# 10-JTAG.net
KiCad netlist of a schematic drawn in Altium Designer
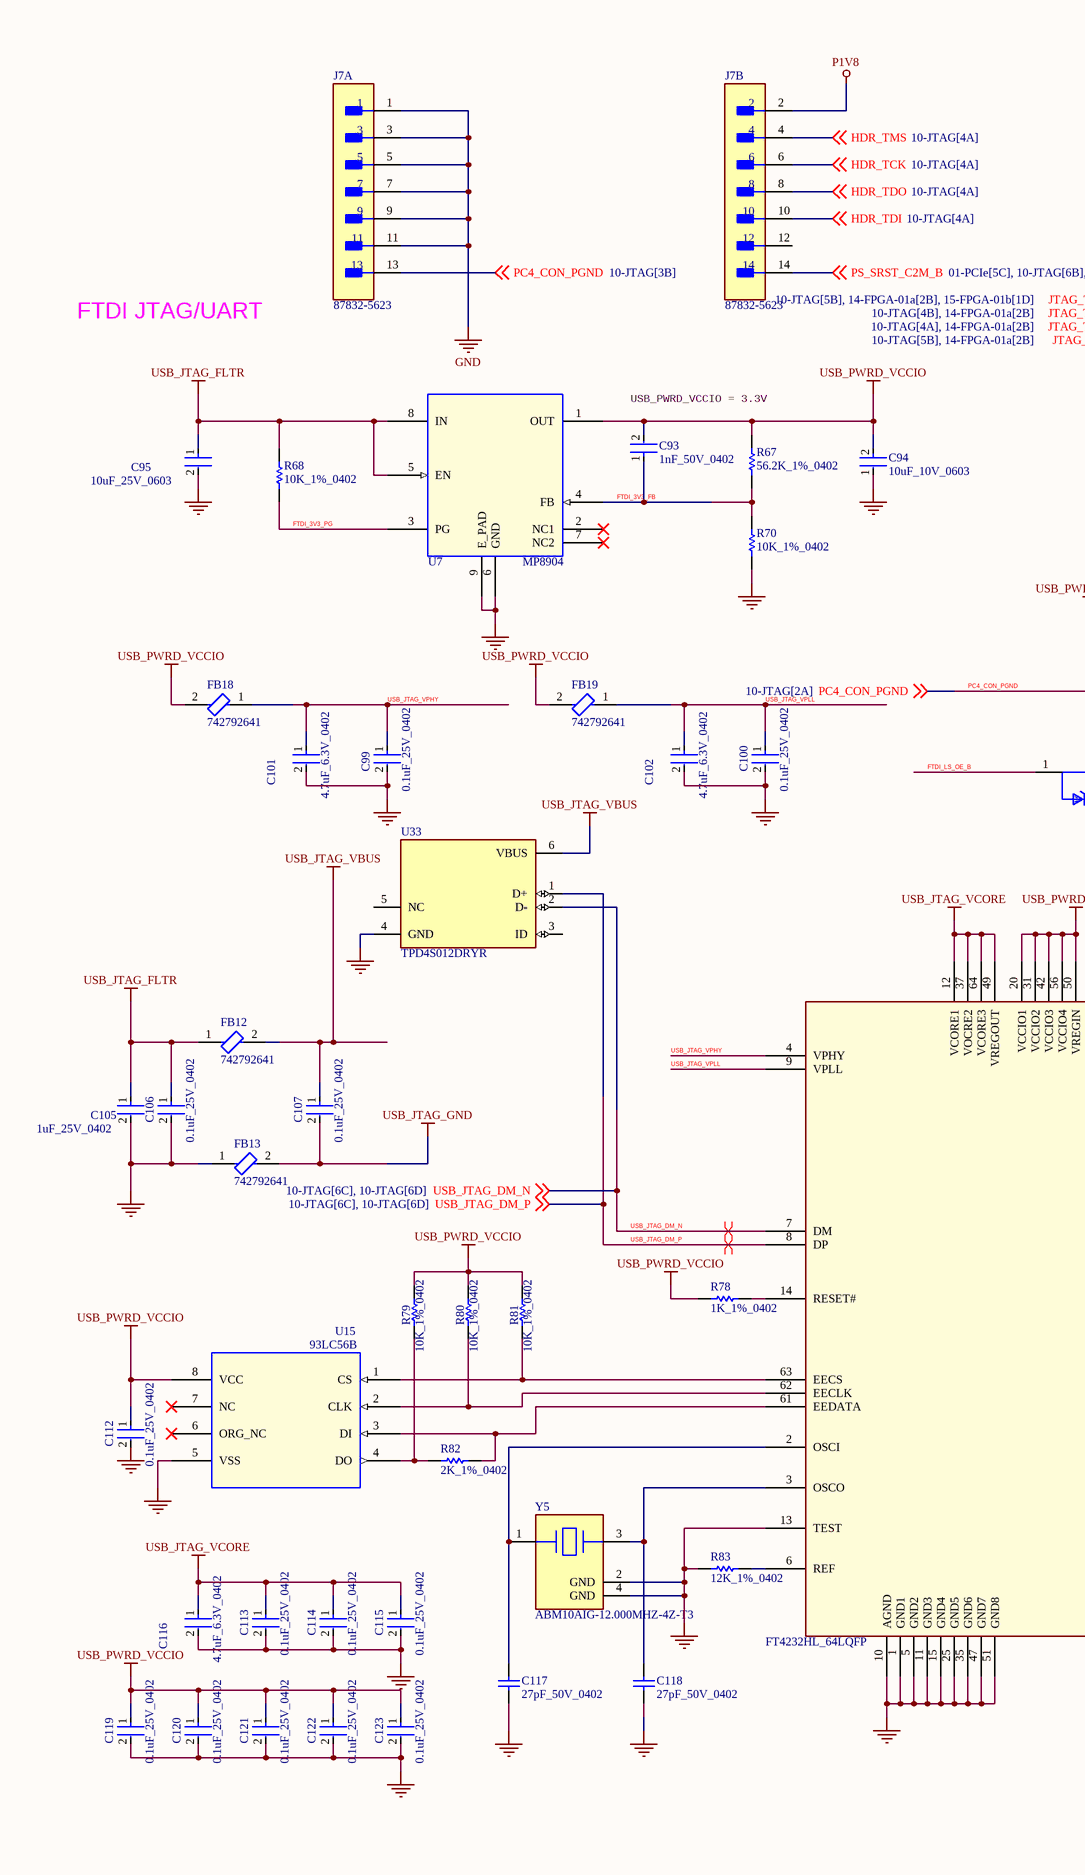
[diagram p0: 10-JTAG.SchDoc, left]
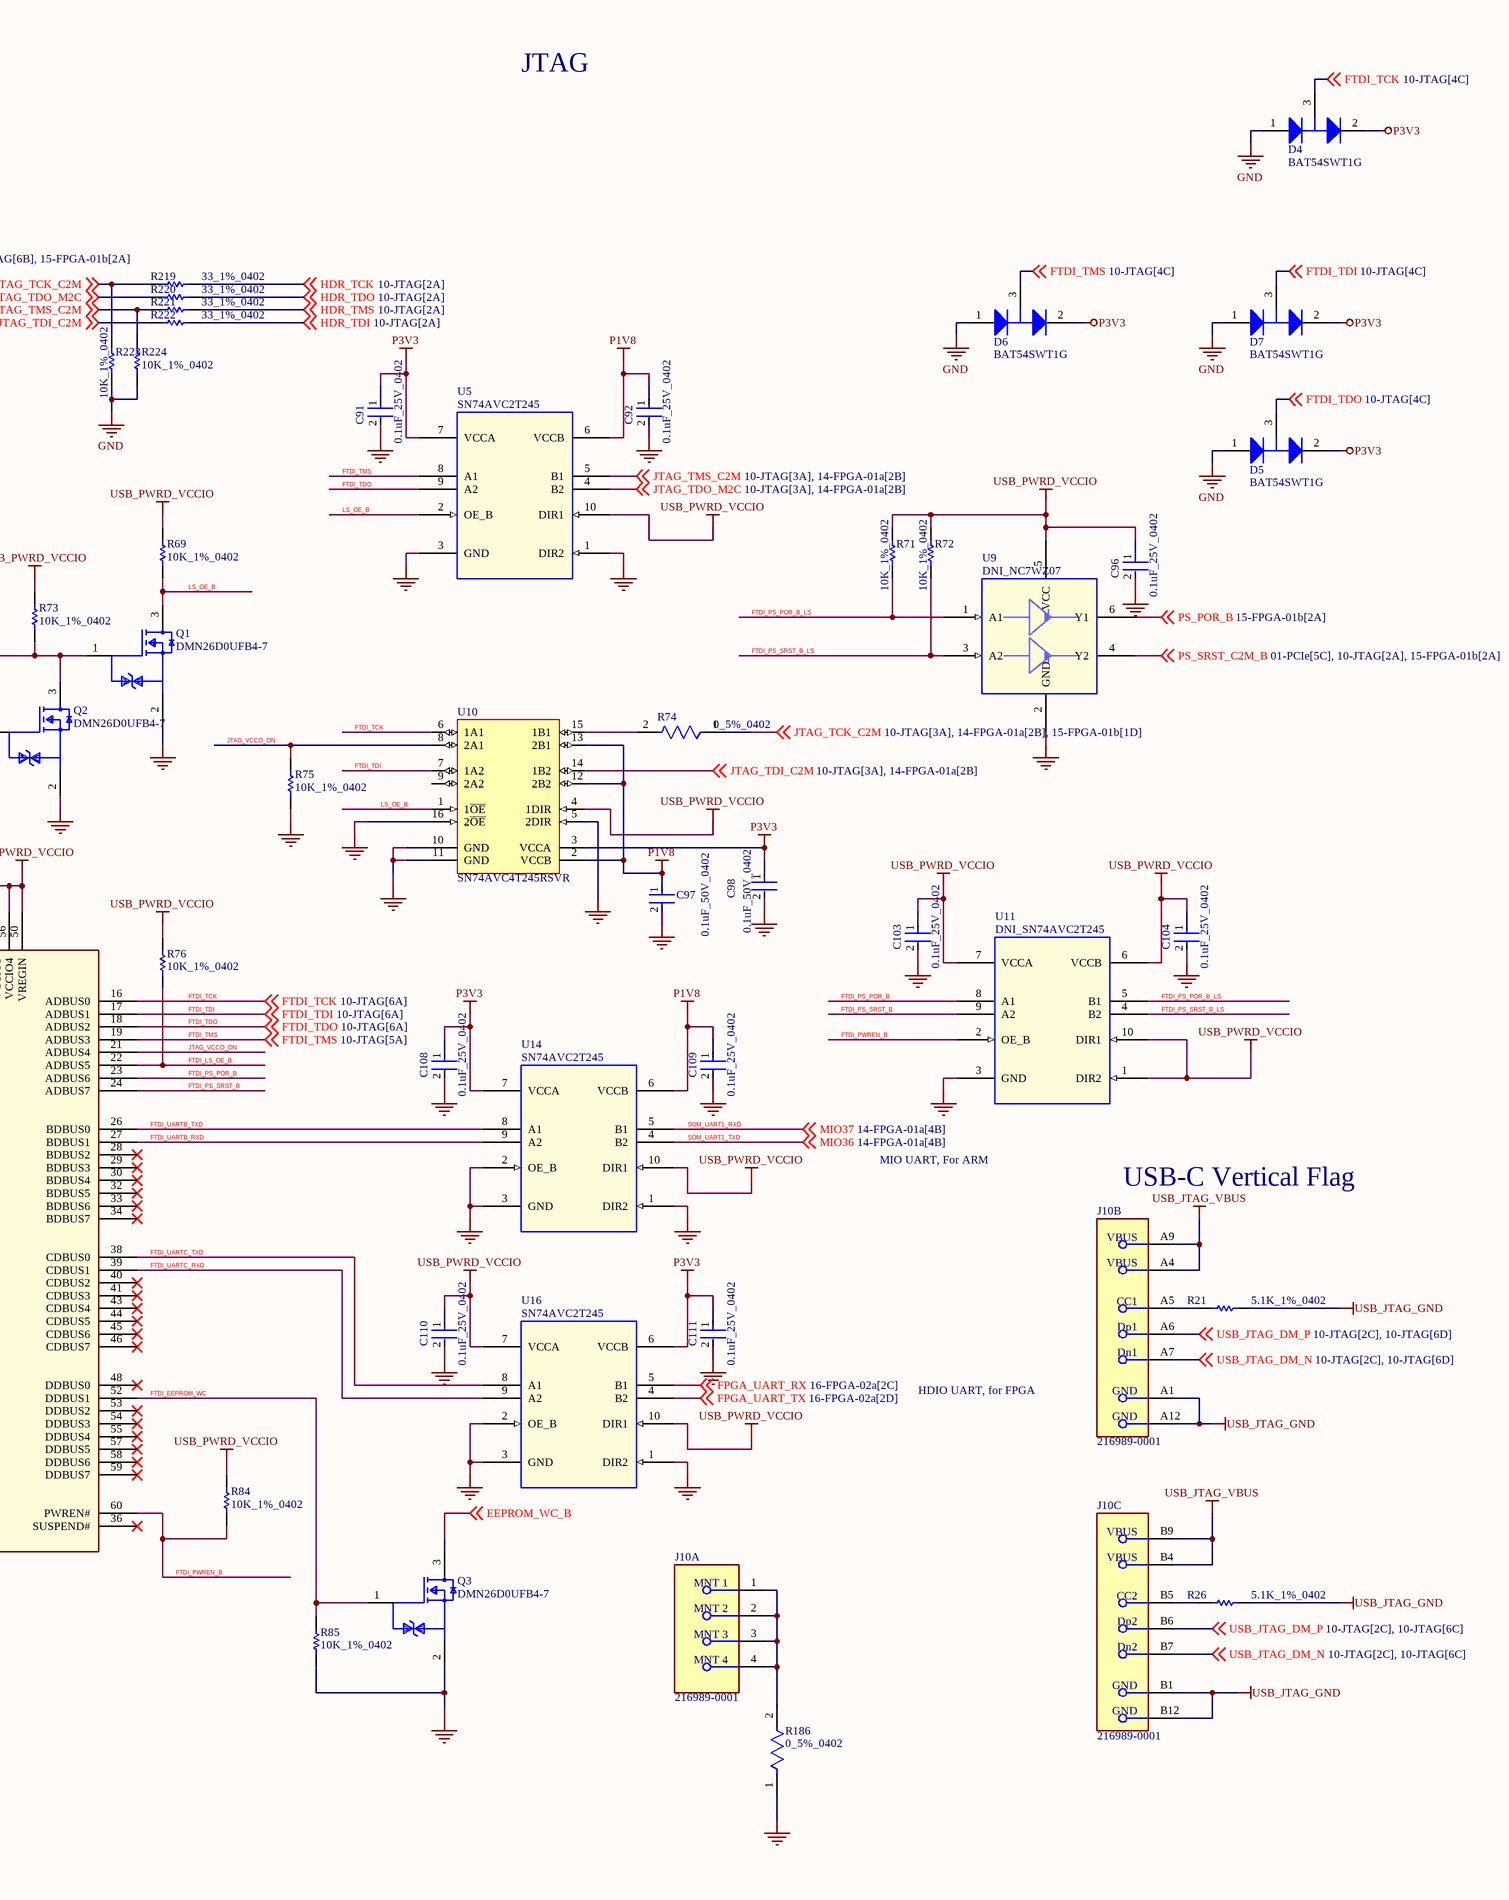
[diagram p1: 10-JTAG.SchDoc, right]

(export (version "E")
  (design (tool "Eeschema 10.0.6"))
  (components
    (comp (ref "C91")
      (value "0.1uF_25V_0402")
      (footprint "FP-0402-L_1_0_1-W_0_5_0_1-IPC_C")
      (description "General Purpose Ceramic Capacitor, 0402, 100nF, 10%, X7R, 15%, 25V")
      (fields (field (name "VOLTAGE") "25V") (field (name "TOLERANCE") "10%"))
      (libsource (lib "Altium Content Vault") (part "b4654b650e69147ec39a6b967a45e02"))
    )
    (comp (ref "C92")
      (value "0.1uF_25V_0402")
      (footprint "FP-0402-L_1_0_1-W_0_5_0_1-IPC_C")
      (description "General Purpose Ceramic Capacitor, 0402, 100nF, 10%, X7R, 15%, 25V")
      (fields (field (name "VOLTAGE") "25V") (field (name "TOLERANCE") "10%"))
      (libsource (lib "Altium Content Vault") (part "b4654b650e69147ec39a6b967a45e02"))
    )
    (comp (ref "C93")
      (value "1nF_50V_0402")
      (footprint "FP-CGA2B-MFG")
      (description "Cap Ceramic 1nF 50V X7R 10% Pad SMD 0402 +125°C Automotive T/R")
      (fields (field (name "TOLERANCE") "10%"))
      (libsource (lib "Altium Content Vault") (part "b4654b650e69147ec39a6b967a45e02"))
    )
    (comp (ref "C94")
      (value "10uF_10V_0603")
      (footprint "FP-C1608-080-0_1-MFG")
      (description "Multilayer Ceramic Capacitors 10μF ±10% 10V X5R SMD 0603")
      (fields (field (name "VOLTAGE") "10V") (field (name "TOLERANCE") "10%"))
      (libsource (lib "Altium Content Vault") (part "236180d848d6139a670b325ea6854c9"))
    )
    (comp (ref "C95")
      (value "10uF_25V_0603")
      (footprint "FP-CL10-IPC_C")
      (description "Cap Ceramic 10uF 25V X5R ±20% Pad SMD 0603 +85°C T/R")
      (fields (field (name "TOLERANCE") "20%"))
      (libsource (lib "Altium Content Vault") (part "b4654b650e69147ec39a6b967a45e02"))
    )
    (comp (ref "C96")
      (value "0.1uF_25V_0402")
      (footprint "FP-0402-L_1_0_1-W_0_5_0_1-IPC_C")
      (description "General Purpose Ceramic Capacitor, 0402, 100nF, 10%, X7R, 15%, 25V")
      (fields (field (name "VOLTAGE") "25V") (field (name "TOLERANCE") "10%"))
      (libsource (lib "Altium Content Vault") (part "b4654b650e69147ec39a6b967a45e02"))
    )
    (comp (ref "C97")
      (value "0.1uF_50V_0402")
      (footprint "FP-C1005-050-0_05-IPC_C")
      (description "Multilayer Ceramic Capacitors 100nF ±10% 50V X7R SMD 0402")
      (fields (field (name "VOLTAGE") "50V") (field (name "TOLERANCE") "10%"))
      (libsource (lib "Altium Content Vault") (part "b4654b650e69147ec39a6b967a45e02"))
    )
    (comp (ref "C98")
      (value "0.1uF_50V_0402")
      (footprint "FP-C1005-050-0_05-IPC_C")
      (description "Multilayer Ceramic Capacitors 100nF ±10% 50V X7R SMD 0402")
      (fields (field (name "VOLTAGE") "50V") (field (name "TOLERANCE") "10%"))
      (libsource (lib "Altium Content Vault") (part "b4654b650e69147ec39a6b967a45e02"))
    )
    (comp (ref "C99")
      (value "0.1uF_25V_0402")
      (footprint "FP-0402-L_1_0_1-W_0_5_0_1-IPC_C")
      (description "General Purpose Ceramic Capacitor, 0402, 100nF, 10%, X7R, 15%, 25V")
      (fields (field (name "VOLTAGE") "25V") (field (name "TOLERANCE") "10%"))
      (libsource (lib "Altium Content Vault") (part "b4654b650e69147ec39a6b967a45e02"))
    )
    (comp (ref "C100")
      (value "0.1uF_25V_0402")
      (footprint "FP-0402-L_1_0_1-W_0_5_0_1-IPC_C")
      (description "General Purpose Ceramic Capacitor, 0402, 100nF, 10%, X7R, 15%, 25V")
      (fields (field (name "VOLTAGE") "25V") (field (name "TOLERANCE") "10%"))
      (libsource (lib "Altium Content Vault") (part "b4654b650e69147ec39a6b967a45e02"))
    )
    (comp (ref "C101")
      (value "4.7uF_6.3V_0402")
      (footprint "FP-C1005-050-0_15-IPC_C")
      (description "CAP CER 4.7UF 6.3V X5R 0402")
      (fields (field (name "VOLTAGE") "6.3V") (field (name "TOLERANCE") "20%"))
      (libsource (lib "Altium Content Vault") (part "02cd4be3c70576c341d710602a673aa"))
    )
    (comp (ref "C102")
      (value "4.7uF_6.3V_0402")
      (footprint "FP-C1005-050-0_15-IPC_C")
      (description "CAP CER 4.7UF 6.3V X5R 0402")
      (fields (field (name "VOLTAGE") "6.3V") (field (name "TOLERANCE") "20%"))
      (libsource (lib "Altium Content Vault") (part "02cd4be3c70576c341d710602a673aa"))
    )
    (comp (ref "C103")
      (value "0.1uF_25V_0402")
      (footprint "FP-0402-L_1_0_1-W_0_5_0_1-IPC_C")
      (description "General Purpose Ceramic Capacitor, 0402, 100nF, 10%, X7R, 15%, 25V")
      (fields (field (name "VOLTAGE") "25V") (field (name "TOLERANCE") "10%"))
      (libsource (lib "Altium Content Vault") (part "b4654b650e69147ec39a6b967a45e02"))
    )
    (comp (ref "C104")
      (value "0.1uF_25V_0402")
      (footprint "FP-0402-L_1_0_1-W_0_5_0_1-IPC_C")
      (description "General Purpose Ceramic Capacitor, 0402, 100nF, 10%, X7R, 15%, 25V")
      (fields (field (name "VOLTAGE") "25V") (field (name "TOLERANCE") "10%"))
      (libsource (lib "Altium Content Vault") (part "b4654b650e69147ec39a6b967a45e02"))
    )
    (comp (ref "C105")
      (value "1uF_25V_0402")
      (footprint "FP-CL542-IPC_C")
      (description "Cap Ceramic 1uF 25V X5R ±10% SMD 0402 +85°C Paper T/R")
      (fields (field (name "TOLERANCE") "10%"))
      (libsource (lib "Altium Content Vault") (part "b4654b650e69147ec39a6b967a45e02"))
    )
    (comp (ref "C106")
      (value "0.1uF_25V_0402")
      (footprint "FP-0402-L_1_0_1-W_0_5_0_1-IPC_C")
      (description "General Purpose Ceramic Capacitor, 0402, 100nF, 10%, X7R, 15%, 25V")
      (fields (field (name "VOLTAGE") "25V") (field (name "TOLERANCE") "10%"))
      (libsource (lib "Altium Content Vault") (part "b4654b650e69147ec39a6b967a45e02"))
    )
    (comp (ref "C107")
      (value "0.1uF_25V_0402")
      (footprint "FP-0402-L_1_0_1-W_0_5_0_1-IPC_C")
      (description "General Purpose Ceramic Capacitor, 0402, 100nF, 10%, X7R, 15%, 25V")
      (fields (field (name "VOLTAGE") "25V") (field (name "TOLERANCE") "10%"))
      (libsource (lib "Altium Content Vault") (part "b4654b650e69147ec39a6b967a45e02"))
    )
    (comp (ref "C108")
      (value "0.1uF_25V_0402")
      (footprint "FP-0402-L_1_0_1-W_0_5_0_1-IPC_C")
      (description "General Purpose Ceramic Capacitor, 0402, 100nF, 10%, X7R, 15%, 25V")
      (fields (field (name "VOLTAGE") "25V") (field (name "TOLERANCE") "10%"))
      (libsource (lib "Altium Content Vault") (part "b4654b650e69147ec39a6b967a45e02"))
    )
    (comp (ref "C109")
      (value "0.1uF_25V_0402")
      (footprint "FP-0402-L_1_0_1-W_0_5_0_1-IPC_C")
      (description "General Purpose Ceramic Capacitor, 0402, 100nF, 10%, X7R, 15%, 25V")
      (fields (field (name "VOLTAGE") "25V") (field (name "TOLERANCE") "10%"))
      (libsource (lib "Altium Content Vault") (part "b4654b650e69147ec39a6b967a45e02"))
    )
    (comp (ref "C110")
      (value "0.1uF_25V_0402")
      (footprint "FP-0402-L_1_0_1-W_0_5_0_1-IPC_C")
      (description "General Purpose Ceramic Capacitor, 0402, 100nF, 10%, X7R, 15%, 25V")
      (fields (field (name "VOLTAGE") "25V") (field (name "TOLERANCE") "10%"))
      (libsource (lib "Altium Content Vault") (part "b4654b650e69147ec39a6b967a45e02"))
    )
    (comp (ref "C111")
      (value "0.1uF_25V_0402")
      (footprint "FP-0402-L_1_0_1-W_0_5_0_1-IPC_C")
      (description "General Purpose Ceramic Capacitor, 0402, 100nF, 10%, X7R, 15%, 25V")
      (fields (field (name "VOLTAGE") "25V") (field (name "TOLERANCE") "10%"))
      (libsource (lib "Altium Content Vault") (part "b4654b650e69147ec39a6b967a45e02"))
    )
    (comp (ref "C112")
      (value "0.1uF_25V_0402")
      (footprint "FP-0402-L_1_0_1-W_0_5_0_1-IPC_C")
      (description "General Purpose Ceramic Capacitor, 0402, 100nF, 10%, X7R, 15%, 25V")
      (fields (field (name "VOLTAGE") "25V") (field (name "TOLERANCE") "10%"))
      (libsource (lib "Altium Content Vault") (part "b4654b650e69147ec39a6b967a45e02"))
    )
    (comp (ref "C113")
      (value "0.1uF_25V_0402")
      (footprint "FP-0402-L_1_0_1-W_0_5_0_1-IPC_C")
      (description "General Purpose Ceramic Capacitor, 0402, 100nF, 10%, X7R, 15%, 25V")
      (fields (field (name "VOLTAGE") "25V") (field (name "TOLERANCE") "10%"))
      (libsource (lib "Altium Content Vault") (part "b4654b650e69147ec39a6b967a45e02"))
    )
    (comp (ref "C114")
      (value "0.1uF_25V_0402")
      (footprint "FP-0402-L_1_0_1-W_0_5_0_1-IPC_C")
      (description "General Purpose Ceramic Capacitor, 0402, 100nF, 10%, X7R, 15%, 25V")
      (fields (field (name "VOLTAGE") "25V") (field (name "TOLERANCE") "10%"))
      (libsource (lib "Altium Content Vault") (part "b4654b650e69147ec39a6b967a45e02"))
    )
    (comp (ref "C115")
      (value "0.1uF_25V_0402")
      (footprint "FP-0402-L_1_0_1-W_0_5_0_1-IPC_C")
      (description "General Purpose Ceramic Capacitor, 0402, 100nF, 10%, X7R, 15%, 25V")
      (fields (field (name "VOLTAGE") "25V") (field (name "TOLERANCE") "10%"))
      (libsource (lib "Altium Content Vault") (part "b4654b650e69147ec39a6b967a45e02"))
    )
    (comp (ref "C116")
      (value "4.7uF_6.3V_0402")
      (footprint "FP-C1005-050-0_15-IPC_C")
      (description "CAP CER 4.7UF 6.3V X5R 0402")
      (fields (field (name "VOLTAGE") "6.3V") (field (name "TOLERANCE") "20%"))
      (libsource (lib "Altium Content Vault") (part "02cd4be3c70576c341d710602a673aa"))
    )
    (comp (ref "C117")
      (value "27pF_50V_0402")
      (footprint "CAPC1005X55X25LL05T10")
      (fields (field (name "PART NUMBER") "GRM1555C1H270JA01D") (field (name "MANUFACTURER") "Murata"))
      (libsource (lib "Altium Content Vault") (part "CAP"))
    )
    (comp (ref "C118")
      (value "27pF_50V_0402")
      (footprint "CAPC1005X55X25LL05T10")
      (fields (field (name "PART NUMBER") "GRM1555C1H270JA01D") (field (name "MANUFACTURER") "Murata"))
      (libsource (lib "Altium Content Vault") (part "CAP"))
    )
    (comp (ref "C119")
      (value "0.1uF_25V_0402")
      (footprint "FP-0402-L_1_0_1-W_0_5_0_1-IPC_C")
      (description "General Purpose Ceramic Capacitor, 0402, 100nF, 10%, X7R, 15%, 25V")
      (fields (field (name "VOLTAGE") "25V") (field (name "TOLERANCE") "10%"))
      (libsource (lib "Altium Content Vault") (part "b4654b650e69147ec39a6b967a45e02"))
    )
    (comp (ref "C120")
      (value "0.1uF_25V_0402")
      (footprint "FP-0402-L_1_0_1-W_0_5_0_1-IPC_C")
      (description "General Purpose Ceramic Capacitor, 0402, 100nF, 10%, X7R, 15%, 25V")
      (fields (field (name "VOLTAGE") "25V") (field (name "TOLERANCE") "10%"))
      (libsource (lib "Altium Content Vault") (part "b4654b650e69147ec39a6b967a45e02"))
    )
    (comp (ref "C121")
      (value "0.1uF_25V_0402")
      (footprint "FP-0402-L_1_0_1-W_0_5_0_1-IPC_C")
      (description "General Purpose Ceramic Capacitor, 0402, 100nF, 10%, X7R, 15%, 25V")
      (fields (field (name "VOLTAGE") "25V") (field (name "TOLERANCE") "10%"))
      (libsource (lib "Altium Content Vault") (part "b4654b650e69147ec39a6b967a45e02"))
    )
    (comp (ref "C122")
      (value "0.1uF_25V_0402")
      (footprint "FP-0402-L_1_0_1-W_0_5_0_1-IPC_C")
      (description "General Purpose Ceramic Capacitor, 0402, 100nF, 10%, X7R, 15%, 25V")
      (fields (field (name "VOLTAGE") "25V") (field (name "TOLERANCE") "10%"))
      (libsource (lib "Altium Content Vault") (part "b4654b650e69147ec39a6b967a45e02"))
    )
    (comp (ref "C123")
      (value "0.1uF_25V_0402")
      (footprint "FP-0402-L_1_0_1-W_0_5_0_1-IPC_C")
      (description "General Purpose Ceramic Capacitor, 0402, 100nF, 10%, X7R, 15%, 25V")
      (fields (field (name "VOLTAGE") "25V") (field (name "TOLERANCE") "10%"))
      (libsource (lib "Altium Content Vault") (part "b4654b650e69147ec39a6b967a45e02"))
    )
    (comp (ref "D4")
      (value "BAT54SWT1G")
      (footprint "ONSC-SOT-323-3-419-04_V")
      (description "Dual Series Schottky Barrier Diodes, 3-Pin SOT-323, Pb-Free, Tape and Reel")
      (fields (field (name "MANUFACTURER") "On Semiconductor"))
      (libsource (lib "Altium Content Vault") (part "ONSC-D-A1K2C3-3"))
    )
    (comp (ref "D5")
      (value "BAT54SWT1G")
      (footprint "ONSC-SOT-323-3-419-04_V")
      (description "Dual Series Schottky Barrier Diodes, 3-Pin SOT-323, Pb-Free, Tape and Reel")
      (fields (field (name "MANUFACTURER") "On Semiconductor"))
      (libsource (lib "Altium Content Vault") (part "ONSC-D-A1K2C3-3"))
    )
    (comp (ref "D6")
      (value "BAT54SWT1G")
      (footprint "ONSC-SOT-323-3-419-04_V")
      (description "Dual Series Schottky Barrier Diodes, 3-Pin SOT-323, Pb-Free, Tape and Reel")
      (fields (field (name "MANUFACTURER") "On Semiconductor"))
      (libsource (lib "Altium Content Vault") (part "ONSC-D-A1K2C3-3"))
    )
    (comp (ref "D7")
      (value "BAT54SWT1G")
      (footprint "ONSC-SOT-323-3-419-04_V")
      (description "Dual Series Schottky Barrier Diodes, 3-Pin SOT-323, Pb-Free, Tape and Reel")
      (fields (field (name "MANUFACTURER") "On Semiconductor"))
      (libsource (lib "Altium Content Vault") (part "ONSC-D-A1K2C3-3"))
    )
    (comp (ref "FB12")
      (value "742792641")
      (footprint "FP-742792641-MFG")
      (description "FERRITE BEAD 300 OHM 0603 1LN")
      (fields (field (name "TOLERANCE") "25%"))
      (libsource (lib "Altium Content Vault") (part "5f30dd21d616792df468990f7003faa"))
    )
    (comp (ref "FB13")
      (value "742792641")
      (footprint "FP-742792641-MFG")
      (description "FERRITE BEAD 300 OHM 0603 1LN")
      (fields (field (name "TOLERANCE") "25%"))
      (libsource (lib "Altium Content Vault") (part "5f30dd21d616792df468990f7003faa"))
    )
    (comp (ref "FB18")
      (value "742792641")
      (footprint "FP-742792641-MFG")
      (description "FERRITE BEAD 300 OHM 0603 1LN")
      (fields (field (name "TOLERANCE") "25%"))
      (libsource (lib "Altium Content Vault") (part "5f30dd21d616792df468990f7003faa"))
    )
    (comp (ref "FB19")
      (value "742792641")
      (footprint "FP-742792641-MFG")
      (description "FERRITE BEAD 300 OHM 0603 1LN")
      (fields (field (name "TOLERANCE") "25%"))
      (libsource (lib "Altium Content Vault") (part "5f30dd21d616792df468990f7003faa"))
    )
    (comp (ref "J7")
      (value "87832-5623")
      (footprint "FP-87832-5623-MFG")
      (description "CONN HEADER SMD 14POS 2MM")
      (libsource (lib "Altium Content Vault") (part "7644e1a88aa4da17242a9b8d8257442"))
    )
    (comp (ref "J10")
      (value "216989-0001")
      (footprint "FP-216989-0001-MFG")
      (description "CONN RCPT USB2.0 TYPE C 24POS RA")
      (libsource (lib "Altium Content Vault") (part "0223f526f2db1734dda50670d79969c"))
    )
    (comp (ref "Q1")
      (value "DMN26D0UFB4-7")
      (footprint "FP-X2-DFN1006-3-MFG")
      (description "MOSFET N-CH 20V 230MA DFN")
      (fields
        (field (name "MANUFACTURER") "Diodes Inc.")
        (field (name "OCTOPART") "https://octopart.com/dmn26d0ufb4-7-diodes+inc.-17947794")
      )
      (libsource (lib "Altium Content Vault") (part "d9362b6f39ae4a0daf9f934787aad07"))
    )
    (comp (ref "Q2")
      (value "DMN26D0UFB4-7")
      (footprint "FP-X2-DFN1006-3-MFG")
      (description "MOSFET N-CH 20V 230MA DFN")
      (fields
        (field (name "MANUFACTURER") "Diodes Inc.")
        (field (name "OCTOPART") "https://octopart.com/dmn26d0ufb4-7-diodes+inc.-17947794")
      )
      (libsource (lib "Altium Content Vault") (part "d9362b6f39ae4a0daf9f934787aad07"))
    )
    (comp (ref "Q3")
      (value "DMN26D0UFB4-7")
      (footprint "FP-X2-DFN1006-3-MFG")
      (description "MOSFET N-CH 20V 230MA DFN")
      (fields
        (field (name "MANUFACTURER") "Diodes Inc.")
        (field (name "OCTOPART") "https://octopart.com/dmn26d0ufb4-7-diodes+inc.-17947794")
      )
      (libsource (lib "Altium Content Vault") (part "d9362b6f39ae4a0daf9f934787aad07"))
    )
    (comp (ref "R21")
      (value "5.1K_1%_0402")
      (footprint "RESC1005X40X25ML10T10")
      (fields (field (name "MANUFACTURER") "KOA Speer") (field (name "PART NUMBER") "RK73H1ETTP5101F"))
      (libsource (lib "Altium Content Vault") (part "RES"))
    )
    (comp (ref "R26")
      (value "5.1K_1%_0402")
      (footprint "RESC1005X40X25ML10T10")
      (fields (field (name "MANUFACTURER") "KOA Speer") (field (name "PART NUMBER") "RK73H1ETTP5101F"))
      (libsource (lib "Altium Content Vault") (part "RES"))
    )
    (comp (ref "R67")
      (value "56.2K_1%_0402")
      (footprint "RESC1005X40X25LL05T05")
      (fields (field (name "PART NUMBER") "ERJ-2RKF5622X") (field (name "MANUFACTURER") "Panasonic"))
      (libsource (lib "Altium Content Vault") (part "RES"))
    )
    (comp (ref "R68")
      (value "10K_1%_0402")
      (footprint "RESC1005X40X25ML05T05")
      (fields (field (name "PART NUMBER") "ERJ-2GEJ103X") (field (name "MANUFACTURER") "Panasonic"))
      (libsource (lib "Altium Content Vault") (part "RES"))
    )
    (comp (ref "R69")
      (value "10K_1%_0402")
      (footprint "RESC1005X40X25ML05T05")
      (fields (field (name "PART NUMBER") "ERJ-2GEJ103X") (field (name "MANUFACTURER") "Panasonic"))
      (libsource (lib "Altium Content Vault") (part "RES"))
    )
    (comp (ref "R70")
      (value "10K_1%_0402")
      (footprint "RESC1005X40X25ML05T05")
      (fields (field (name "PART NUMBER") "ERJ-2GEJ103X") (field (name "MANUFACTURER") "Panasonic"))
      (libsource (lib "Altium Content Vault") (part "RES"))
    )
    (comp (ref "R71")
      (value "10K_1%_0402")
      (footprint "RESC1005X40X25ML05T05")
      (fields (field (name "PART NUMBER") "ERJ-2GEJ103X") (field (name "MANUFACTURER") "Panasonic"))
      (libsource (lib "Altium Content Vault") (part "RES"))
    )
    (comp (ref "R72")
      (value "10K_1%_0402")
      (footprint "RESC1005X40X25ML05T05")
      (fields (field (name "PART NUMBER") "ERJ-2GEJ103X") (field (name "MANUFACTURER") "Panasonic"))
      (libsource (lib "Altium Content Vault") (part "RES"))
    )
    (comp (ref "R73")
      (value "10K_1%_0402")
      (footprint "RESC1005X40X25ML05T05")
      (fields (field (name "PART NUMBER") "ERJ-2GEJ103X") (field (name "MANUFACTURER") "Panasonic"))
      (libsource (lib "Altium Content Vault") (part "RES"))
    )
    (comp (ref "R74")
      (value "0_5%_0402")
      (footprint "FP-AC0402-0_37-IPC_B")
      (description "RESISTOR 0402 JUMPER ZERO OHM")
      (fields (field (name "TOLERANCE") "1%"))
      (libsource (lib "Altium Content Vault") (part "1029c3af85768c4190bb7ad29bc67b5"))
    )
    (comp (ref "R75")
      (value "10K_1%_0402")
      (footprint "RESC1005X40X25ML05T05")
      (fields (field (name "PART NUMBER") "ERJ-2GEJ103X") (field (name "MANUFACTURER") "Panasonic"))
      (libsource (lib "Altium Content Vault") (part "RES"))
    )
    (comp (ref "R76")
      (value "10K_1%_0402")
      (footprint "RESC1005X40X25ML05T05")
      (fields (field (name "PART NUMBER") "ERJ-2GEJ103X") (field (name "MANUFACTURER") "Panasonic"))
      (libsource (lib "Altium Content Vault") (part "RES"))
    )
    (comp (ref "R78")
      (value "1K_1%_0402")
      (footprint "RESC1005X40X25NL05T05")
      (fields (field (name "MANUFACTURER") "Vishay Dale") (field (name "PART NUMBER") "CRCW04021K00FKTD"))
      (libsource (lib "Altium Content Vault") (part "RES"))
    )
    (comp (ref "R79")
      (value "10K_1%_0402")
      (footprint "RESC1005X40X25ML05T05")
      (fields (field (name "PART NUMBER") "ERJ-2GEJ103X") (field (name "MANUFACTURER") "Panasonic"))
      (libsource (lib "Altium Content Vault") (part "RES"))
    )
    (comp (ref "R80")
      (value "10K_1%_0402")
      (footprint "RESC1005X40X25ML05T05")
      (fields (field (name "PART NUMBER") "ERJ-2GEJ103X") (field (name "MANUFACTURER") "Panasonic"))
      (libsource (lib "Altium Content Vault") (part "RES"))
    )
    (comp (ref "R81")
      (value "10K_1%_0402")
      (footprint "RESC1005X40X25ML05T05")
      (fields (field (name "PART NUMBER") "ERJ-2GEJ103X") (field (name "MANUFACTURER") "Panasonic"))
      (libsource (lib "Altium Content Vault") (part "RES"))
    )
    (comp (ref "R82")
      (value "2K_1%_0402")
      (footprint "RESC1005X40X25LL10T10")
      (fields (field (name "MANUFACTURER") "Multicomp") (field (name "PART NUMBER") "MC00625W040212K"))
      (libsource (lib "Altium Content Vault") (part "RES"))
    )
    (comp (ref "R83")
      (value "12K_1%_0402")
      (footprint "RESC1005X40X25ML10T10")
      (fields (field (name "MANUFACTURER") "KOA Speer") (field (name "PART NUMBER") "RK73H1ETTP1202F"))
      (libsource (lib "Altium Content Vault") (part "RES"))
    )
    (comp (ref "R84")
      (value "10K_1%_0402")
      (footprint "RESC1005X40X25ML05T05")
      (fields (field (name "PART NUMBER") "ERJ-2GEJ103X") (field (name "MANUFACTURER") "Panasonic"))
      (libsource (lib "Altium Content Vault") (part "RES"))
    )
    (comp (ref "R85")
      (value "10K_1%_0402")
      (footprint "RESC1005X40X25ML05T05")
      (fields (field (name "PART NUMBER") "ERJ-2GEJ103X") (field (name "MANUFACTURER") "Panasonic"))
      (libsource (lib "Altium Content Vault") (part "RES"))
    )
    (comp (ref "R186")
      (value "0_5%_0402")
      (footprint "FP-AC0402-0_37-IPC_B")
      (description "RESISTOR 0402 JUMPER ZERO OHM")
      (fields (field (name "TOLERANCE") "1%"))
      (libsource (lib "Altium Content Vault") (part "1029c3af85768c4190bb7ad29bc67b5"))
    )
    (comp (ref "R219")
      (value "33_1%_0402")
      (footprint "RESC1005X40X25NL05T10")
      (fields (field (name "PART NUMBER") "RC0402FR-1333RL") (field (name "MANUFACTURER") "Yageo"))
      (libsource (lib "Altium Content Vault") (part "RES"))
    )
    (comp (ref "R220")
      (value "33_1%_0402")
      (footprint "RESC1005X40X25NL05T10")
      (fields (field (name "PART NUMBER") "RC0402FR-1333RL") (field (name "MANUFACTURER") "Yageo"))
      (libsource (lib "Altium Content Vault") (part "RES"))
    )
    (comp (ref "R221")
      (value "33_1%_0402")
      (footprint "RESC1005X40X25NL05T10")
      (fields (field (name "PART NUMBER") "RC0402FR-1333RL") (field (name "MANUFACTURER") "Yageo"))
      (libsource (lib "Altium Content Vault") (part "RES"))
    )
    (comp (ref "R222")
      (value "33_1%_0402")
      (footprint "RESC1005X40X25NL05T10")
      (fields (field (name "PART NUMBER") "RC0402FR-1333RL") (field (name "MANUFACTURER") "Yageo"))
      (libsource (lib "Altium Content Vault") (part "RES"))
    )
    (comp (ref "R223")
      (value "10K_1%_0402")
      (footprint "RESC1005X40X25ML05T05")
      (fields (field (name "PART NUMBER") "ERJ-2GEJ103X") (field (name "MANUFACTURER") "Panasonic"))
      (libsource (lib "Altium Content Vault") (part "RES"))
    )
    (comp (ref "R224")
      (value "10K_1%_0402")
      (footprint "RESC1005X40X25ML05T05")
      (fields (field (name "PART NUMBER") "ERJ-2GEJ103X") (field (name "MANUFACTURER") "Panasonic"))
      (libsource (lib "Altium Content Vault") (part "RES"))
    )
    (comp (ref "U5")
      (value "SN74AVC2T245")
      (footprint "QFN40P140X180X55-10")
      (description "IC Lvl Trans 2-Bit Bidir 500Mbps 1.2-3.6V 50mA UQFN-10")
      (fields
        (field (name "MANUFACTURER") "TEXAS INSTRUMENTS")
        (field (name "AGILE PART NUMBER") "ICS-00048-01")
      )
      (libsource (lib "*") (part "SN74AVC2T245"))
    )
    (comp (ref "U7")
      (value "MP8904")
      (footprint "QFN_MP8904DD_8")
      (description "IC LDO 6.5V 500mA Adj QFN-8")
      (fields
        (field (name "MANUFACTURER") "Monolithic Power Systems Inc.")
        (field (name "AGILE PART NUMBER") "ICS-00581-01")
      )
      (libsource (lib "*") (part "MP8904"))
    )
    (comp (ref "U9")
      (value "DNI_NC7WZ07")
      (footprint "SC70_6")
      (description "IC Buffer Dual 5V 50mA 3.9nSec SC70-6 Open Drain")
      (fields
        (field (name "MANUFACTURER") "ON Semiconductor")
        (field (name "AGILE PART NUMBER") "ICS-00102-01")
      )
      (libsource (lib "*") (part "NC7WZ07"))
    )
    (comp (ref "U10")
      (value "SN74AVC4T245RSVR")
      (footprint "RSV0016A_V")
      (fields (field (name "MANUFACTURER") "Texas Instruments"))
      (libsource (lib "Altium Content Vault") (part "TI-SN74AVC4T245-UQFN-16"))
    )
    (comp (ref "U11")
      (value "DNI_SN74AVC2T245")
      (footprint "QFN40P140X180X55-10")
      (description "IC Lvl Trans 2-Bit Bidir 500Mbps 1.2-3.6V 50mA UQFN-10")
      (fields
        (field (name "MANUFACTURER") "TEXAS INSTRUMENTS")
        (field (name "AGILE PART NUMBER") "ICS-00048-01")
      )
      (libsource (lib "*") (part "SN74AVC2T245"))
    )
    (comp (ref "U13")
      (value "FT4232HL_64LQFP")
      (footprint "LQFP_64")
      (libsource (lib "SCK-KR_revA02_Library") (part "FT4232HL"))
    )
    (comp (ref "U14")
      (value "SN74AVC2T245")
      (footprint "QFN40P140X180X55-10")
      (description "IC Lvl Trans 2-Bit Bidir 500Mbps 1.2-3.6V 50mA UQFN-10")
      (fields
        (field (name "MANUFACTURER") "TEXAS INSTRUMENTS")
        (field (name "AGILE PART NUMBER") "ICS-00048-01")
      )
      (libsource (lib "*") (part "SN74AVC2T245"))
    )
    (comp (ref "U15")
      (value "93LC56B")
      (footprint "SOIC8P127W390")
      (description "IC EEPROM 2Kb 128x16-Bit Serial 2MHz 2.5V SOIC-8")
      (fields (field (name "MANUFACTURER") "MICROCHIP") (field (name "AGILE PART NUMBER") "ICS-00335-01"))
      (libsource (lib "*") (part "93LC56B"))
    )
    (comp (ref "U16")
      (value "SN74AVC2T245")
      (footprint "QFN40P140X180X55-10")
      (description "IC Lvl Trans 2-Bit Bidir 500Mbps 1.2-3.6V 50mA UQFN-10")
      (fields
        (field (name "MANUFACTURER") "TEXAS INSTRUMENTS")
        (field (name "AGILE PART NUMBER") "ICS-00048-01")
      )
      (libsource (lib "*") (part "SN74AVC2T245"))
    )
    (comp (ref "U33")
      (value "TPD4S012DRYR")
      (footprint "FP-DRY0006A-MFG")
      (description "TVS DIODE 5.5V 6SON")
      (libsource (lib "Altium Content Vault") (part "0f51f1bc734c3fed0021f16fcfaf2e1"))
    )
    (comp (ref "Y5")
      (value "ABM10AIG-12.000MHZ-4Z-T3")
      (footprint "FP-ABM10AIG-MFG")
      (description "Crystal 12MHz ±30ppm 10pF SMD-4 2.5mm x 2mm Automotive")
      (libsource (lib "Altium Content Vault") (part "40c3c19da1ce8e2d75e34138d1085e7"))
    )
  )
  (nets
    (net (code "1") (name "/FTDI_3V3_FB") (class "Default")
      (node (ref "C93") (pin "1") (pinfunction "1_1") (pintype "passive"))
      (node (ref "R67") (pin "1") (pinfunction "1_1") (pintype "passive"))
      (node (ref "R70") (pin "2") (pinfunction "2_2") (pintype "passive"))
      (node (ref "U7") (pin "4") (pinfunction "FB_4") (pintype "input"))
    )
    (net (code "2") (name "/FTDI_3V3_PG") (class "Default")
      (node (ref "R68") (pin "1") (pinfunction "1_1") (pintype "passive"))
      (node (ref "U7") (pin "3") (pinfunction "PG_3") (pintype "open_collector"))
    )
    (net (code "3") (name "/FTDI_EEPROM_WC") (class "Default")
      (node (ref "Q3") (pin "1") (pinfunction "G_1") (pintype "passive"))
      (node (ref "R85") (pin "2") (pinfunction "2_2") (pintype "passive"))
      (node (ref "U13") (pin "52") (pinfunction "DDBUS1_52") (pintype "passive"))
    )
    (net (code "4") (name "/FTDI_LS_OE_B") (class "Default")
      (node (ref "Q2") (pin "1") (pinfunction "G_1") (pintype "passive"))
      (node (ref "R76") (pin "1") (pinfunction "1_1") (pintype "passive"))
      (node (ref "U13") (pin "22") (pinfunction "ADBUS5_22") (pintype "passive"))
    )
    (net (code "5") (name "/FTDI_PS_POR_B") (class "Default")
      (node (ref "U11") (pin "8") (pinfunction "A1_8") (pintype "passive"))
      (node (ref "U13") (pin "23") (pinfunction "ADBUS6_23") (pintype "passive"))
    )
    (net (code "6") (name "/FTDI_PS_POR_B_LS") (class "Default")
      (node (ref "R71") (pin "1") (pinfunction "1_1") (pintype "passive"))
      (node (ref "U11") (pin "5") (pinfunction "B1_5") (pintype "passive"))
      (node (ref "U9") (pin "1") (pinfunction "A1_1") (pintype "input"))
    )
    (net (code "7") (name "/FTDI_PS_SRST_B") (class "Default")
      (node (ref "U11") (pin "9") (pinfunction "A2_9") (pintype "passive"))
      (node (ref "U13") (pin "24") (pinfunction "ADBUS7_24") (pintype "passive"))
    )
    (net (code "8") (name "/FTDI_PS_SRST_B_LS") (class "Default")
      (node (ref "R72") (pin "1") (pinfunction "1_1") (pintype "passive"))
      (node (ref "U11") (pin "4") (pinfunction "B2_4") (pintype "passive"))
      (node (ref "U9") (pin "3") (pinfunction "A2_3") (pintype "input"))
    )
    (net (code "9") (name "/FTDI_PWREN_B") (class "Default")
      (node (ref "R84") (pin "1") (pinfunction "1_1") (pintype "passive"))
      (node (ref "U11") (pin "2") (pinfunction "OE_B_2") (pintype "input"))
      (node (ref "U13") (pin "60") (pinfunction "PWREN#_60") (pintype "passive"))
    )
    (net (code "10") (name "/FTDI_UARTB_RXD") (class "Default")
      (node (ref "U13") (pin "27") (pinfunction "BDBUS1_27") (pintype "passive"))
      (node (ref "U14") (pin "9") (pinfunction "A2_9") (pintype "passive"))
    )
    (net (code "11") (name "/FTDI_UARTB_TXD") (class "Default")
      (node (ref "U13") (pin "26") (pinfunction "BDBUS0_26") (pintype "passive"))
      (node (ref "U14") (pin "8") (pinfunction "A1_8") (pintype "passive"))
    )
    (net (code "12") (name "/FTDI_UARTC_RXD") (class "Default")
      (node (ref "U13") (pin "39") (pinfunction "CDBUS1_39") (pintype "passive"))
      (node (ref "U16") (pin "9") (pinfunction "A2_9") (pintype "passive"))
    )
    (net (code "13") (name "/FTDI_UARTC_TXD") (class "Default")
      (node (ref "U13") (pin "38") (pinfunction "CDBUS0_38") (pintype "passive"))
      (node (ref "U16") (pin "8") (pinfunction "A1_8") (pintype "passive"))
    )
    (net (code "14") (name "/JTAG_VCCO_ON") (class "Default")
      (node (ref "R75") (pin "2") (pinfunction "2_2") (pintype "passive"))
      (node (ref "U10") (pin "8") (pinfunction "2A1_8") (pintype "bidirectional"))
      (node (ref "U13") (pin "21") (pinfunction "ADBUS4_21") (pintype "passive"))
    )
    (net (code "15") (name "/LS_OE_B") (class "Default")
      (node (ref "Q1") (pin "3") (pinfunction "D_3") (pintype "passive"))
      (node (ref "R69") (pin "1") (pinfunction "1_1") (pintype "passive"))
      (node (ref "U10") (pin "1") (pinfunction "1~{OE}_1") (pintype "input"))
      (node (ref "U5") (pin "2") (pinfunction "OE_B_2") (pintype "input"))
    )
    (net (code "16") (name "/USB_JTAG_VPHY") (class "Default")
      (node (ref "C101") (pin "1") (pinfunction "1_1") (pintype "passive"))
      (node (ref "C99") (pin "1") (pinfunction "1_1") (pintype "passive"))
      (node (ref "FB18") (pin "1") (pinfunction "1_1") (pintype "passive"))
      (node (ref "U13") (pin "4") (pinfunction "VPHY_4") (pintype "passive"))
    )
    (net (code "17") (name "/USB_JTAG_VPLL") (class "Default")
      (node (ref "C100") (pin "1") (pinfunction "1_1") (pintype "passive"))
      (node (ref "C102") (pin "1") (pinfunction "1_1") (pintype "passive"))
      (node (ref "FB19") (pin "1") (pinfunction "1_1") (pintype "passive"))
      (node (ref "U13") (pin "9") (pinfunction "VPLL_9") (pintype "passive"))
    )
    (net (code "18") (name "EEPROM_WC_B") (class "Default")
      (node (ref "Q3") (pin "3") (pinfunction "D_3") (pintype "passive"))
    )
    (net (code "19") (name "FPGA_UART_RX") (class "Default")
      (node (ref "U16") (pin "5") (pinfunction "B1_5") (pintype "passive"))
    )
    (net (code "20") (name "FPGA_UART_TX") (class "Default")
      (node (ref "U16") (pin "4") (pinfunction "B2_4") (pintype "passive"))
    )
    (net (code "21") (name "FTDI_TCK") (class "Default")
      (node (ref "D4") (pin "3") (pinfunction "K/A_3") (pintype "passive"))
      (node (ref "U10") (pin "6") (pinfunction "1A1_6") (pintype "bidirectional"))
      (node (ref "U13") (pin "16") (pinfunction "ADBUS0_16") (pintype "passive"))
    )
    (net (code "22") (name "FTDI_TDI") (class "Default")
      (node (ref "D7") (pin "3") (pinfunction "K/A_3") (pintype "passive"))
      (node (ref "U10") (pin "7") (pinfunction "1A2_7") (pintype "bidirectional"))
      (node (ref "U13") (pin "17") (pinfunction "ADBUS1_17") (pintype "passive"))
    )
    (net (code "23") (name "FTDI_TDO") (class "Default")
      (node (ref "D5") (pin "3") (pinfunction "K/A_3") (pintype "passive"))
      (node (ref "U13") (pin "18") (pinfunction "ADBUS2_18") (pintype "passive"))
      (node (ref "U5") (pin "9") (pinfunction "A2_9") (pintype "passive"))
    )
    (net (code "24") (name "FTDI_TMS") (class "Default")
      (node (ref "D6") (pin "3") (pinfunction "K/A_3") (pintype "passive"))
      (node (ref "U13") (pin "19") (pinfunction "ADBUS3_19") (pintype "passive"))
      (node (ref "U5") (pin "8") (pinfunction "A1_8") (pintype "passive"))
    )
    (net (code "25") (name "GND") (class "Default")
      (node (ref "C100") (pin "2") (pinfunction "2_2") (pintype "passive"))
      (node (ref "C101") (pin "2") (pinfunction "2_2") (pintype "passive"))
      (node (ref "C102") (pin "2") (pinfunction "2_2") (pintype "passive"))
      (node (ref "C103") (pin "2") (pinfunction "2_2") (pintype "passive"))
      (node (ref "C104") (pin "2") (pinfunction "2_2") (pintype "passive"))
      (node (ref "C105") (pin "2") (pinfunction "2_2") (pintype "passive"))
      (node (ref "C106") (pin "2") (pinfunction "2_2") (pintype "passive"))
      (node (ref "C108") (pin "2") (pinfunction "2_2") (pintype "passive"))
      (node (ref "C109") (pin "2") (pinfunction "2_2") (pintype "passive"))
      (node (ref "C110") (pin "2") (pinfunction "2_2") (pintype "passive"))
      (node (ref "C111") (pin "2") (pinfunction "2_2") (pintype "passive"))
      (node (ref "C112") (pin "2") (pinfunction "2_2") (pintype "passive"))
      (node (ref "C113") (pin "2") (pinfunction "2_2") (pintype "passive"))
      (node (ref "C114") (pin "2") (pinfunction "2_2") (pintype "passive"))
      (node (ref "C115") (pin "2") (pinfunction "2_2") (pintype "passive"))
      (node (ref "C116") (pin "2") (pinfunction "2_2") (pintype "passive"))
      (node (ref "C117") (pin "1") (pinfunction "1_1") (pintype "passive"))
      (node (ref "C118") (pin "1") (pinfunction "1_1") (pintype "passive"))
      (node (ref "C119") (pin "2") (pinfunction "2_2") (pintype "passive"))
      (node (ref "C120") (pin "2") (pinfunction "2_2") (pintype "passive"))
      (node (ref "C121") (pin "2") (pinfunction "2_2") (pintype "passive"))
      (node (ref "C122") (pin "2") (pinfunction "2_2") (pintype "passive"))
      (node (ref "C123") (pin "2") (pinfunction "2_2") (pintype "passive"))
      (node (ref "C91") (pin "2") (pinfunction "2_2") (pintype "passive"))
      (node (ref "C92") (pin "2") (pinfunction "2_2") (pintype "passive"))
      (node (ref "C94") (pin "1") (pinfunction "1_1") (pintype "passive"))
      (node (ref "C95") (pin "2") (pinfunction "2_2") (pintype "passive"))
      (node (ref "C96") (pin "2") (pinfunction "2_2") (pintype "passive"))
      (node (ref "C97") (pin "2") (pinfunction "2_2") (pintype "passive"))
      (node (ref "C98") (pin "2") (pinfunction "2_2") (pintype "passive"))
      (node (ref "C99") (pin "2") (pinfunction "2_2") (pintype "passive"))
      (node (ref "D4") (pin "1") (pinfunction "A_1") (pintype "passive"))
      (node (ref "D5") (pin "1") (pinfunction "A_1") (pintype "passive"))
      (node (ref "D6") (pin "1") (pinfunction "A_1") (pintype "passive"))
      (node (ref "D7") (pin "1") (pinfunction "A_1") (pintype "passive"))
      (node (ref "FB13") (pin "1") (pinfunction "1_1") (pintype "passive"))
      (node (ref "J7") (pin "1") (pinfunction "1_1") (pintype "passive"))
      (node (ref "J7") (pin "11") (pinfunction "11_11") (pintype "passive"))
      (node (ref "J7") (pin "3") (pinfunction "3_3") (pintype "passive"))
      (node (ref "J7") (pin "5") (pinfunction "5_5") (pintype "passive"))
      (node (ref "J7") (pin "7") (pinfunction "7_7") (pintype "passive"))
      (node (ref "J7") (pin "9") (pinfunction "9_9") (pintype "passive"))
      (node (ref "Q1") (pin "2") (pinfunction "S_2") (pintype "passive"))
      (node (ref "Q2") (pin "2") (pinfunction "S_2") (pintype "passive"))
      (node (ref "Q3") (pin "2") (pinfunction "S_2") (pintype "passive"))
      (node (ref "R186") (pin "1") (pinfunction "1_1") (pintype "passive"))
      (node (ref "R223") (pin "1") (pinfunction "1_1") (pintype "passive"))
      (node (ref "R224") (pin "1") (pinfunction "1_1") (pintype "passive"))
      (node (ref "R70") (pin "1") (pinfunction "1_1") (pintype "passive"))
      (node (ref "R75") (pin "1") (pinfunction "1_1") (pintype "passive"))
      (node (ref "R83") (pin "1") (pinfunction "1_1") (pintype "passive"))
      (node (ref "R85") (pin "1") (pinfunction "1_1") (pintype "passive"))
      (node (ref "U10") (pin "10") (pinfunction "GND_10") (pintype "power_in"))
      (node (ref "U10") (pin "11") (pinfunction "GND_11") (pintype "power_in"))
      (node (ref "U10") (pin "16") (pinfunction "2~{OE}_16") (pintype "input"))
      (node (ref "U10") (pin "5") (pinfunction "2DIR_5") (pintype "input"))
      (node (ref "U11") (pin "3") (pinfunction "GND_3") (pintype "power_in"))
      (node (ref "U13") (pin "1") (pinfunction "GND1_1") (pintype "passive"))
      (node (ref "U13") (pin "10") (pinfunction "AGND_10") (pintype "passive"))
      (node (ref "U13") (pin "11") (pinfunction "GND3_11") (pintype "passive"))
      (node (ref "U13") (pin "13") (pinfunction "TEST_13") (pintype "passive"))
      (node (ref "U13") (pin "15") (pinfunction "GND4_15") (pintype "passive"))
      (node (ref "U13") (pin "25") (pinfunction "GND5_25") (pintype "passive"))
      (node (ref "U13") (pin "35") (pinfunction "GND6_35") (pintype "passive"))
      (node (ref "U13") (pin "47") (pinfunction "GND7_47") (pintype "passive"))
      (node (ref "U13") (pin "5") (pinfunction "GND2_5") (pintype "passive"))
      (node (ref "U13") (pin "51") (pinfunction "GND8_51") (pintype "passive"))
      (node (ref "U14") (pin "1") (pinfunction "DIR2_1") (pintype "input"))
      (node (ref "U14") (pin "2") (pinfunction "OE_B_2") (pintype "input"))
      (node (ref "U14") (pin "3") (pinfunction "GND_3") (pintype "power_in"))
      (node (ref "U15") (pin "5") (pinfunction "VSS_5") (pintype "power_in"))
      (node (ref "U16") (pin "1") (pinfunction "DIR2_1") (pintype "input"))
      (node (ref "U16") (pin "2") (pinfunction "OE_B_2") (pintype "input"))
      (node (ref "U16") (pin "3") (pinfunction "GND_3") (pintype "power_in"))
      (node (ref "U33") (pin "4") (pinfunction "GND_4") (pintype "power_in"))
      (node (ref "U5") (pin "1") (pinfunction "DIR2_1") (pintype "input"))
      (node (ref "U5") (pin "3") (pinfunction "GND_3") (pintype "power_in"))
      (node (ref "U7") (pin "6") (pinfunction "GND_6") (pintype "power_in"))
      (node (ref "U7") (pin "9") (pinfunction "E_PAD_9") (pintype "power_in"))
      (node (ref "U9") (pin "2") (pinfunction "GND_2") (pintype "power_in"))
      (node (ref "Y5") (pin "2") (pinfunction "GND_2") (pintype "power_in"))
      (node (ref "Y5") (pin "4") (pinfunction "GND_4") (pintype "power_in"))
    )
    (net (code "26") (name "HDR_TCK") (class "Default")
      (node (ref "J7") (pin "6") (pinfunction "6_6") (pintype "passive"))
      (node (ref "R219") (pin "2") (pinfunction "2_2") (pintype "passive"))
    )
    (net (code "27") (name "HDR_TDI") (class "Default")
      (node (ref "J7") (pin "10") (pinfunction "10_10") (pintype "passive"))
      (node (ref "R222") (pin "2") (pinfunction "2_2") (pintype "passive"))
    )
    (net (code "28") (name "HDR_TDO") (class "Default")
      (node (ref "J7") (pin "8") (pinfunction "8_8") (pintype "passive"))
      (node (ref "R220") (pin "2") (pinfunction "2_2") (pintype "passive"))
    )
    (net (code "29") (name "HDR_TMS") (class "Default")
      (node (ref "J7") (pin "4") (pinfunction "4_4") (pintype "passive"))
      (node (ref "R221") (pin "2") (pinfunction "2_2") (pintype "passive"))
    )
    (net (code "30") (name "JTAG_TCK_C2M") (class "Default")
      (node (ref "R219") (pin "1") (pinfunction "1_1") (pintype "passive"))
      (node (ref "R223") (pin "2") (pinfunction "2_2") (pintype "passive"))
      (node (ref "R74") (pin "1") (pinfunction "1_1") (pintype "passive"))
    )
    (net (code "31") (name "JTAG_TDI_C2M") (class "Default")
      (node (ref "R222") (pin "1") (pinfunction "1_1") (pintype "passive"))
      (node (ref "U10") (pin "14") (pinfunction "1B2_14") (pintype "bidirectional"))
    )
    (net (code "32") (name "JTAG_TDO_M2C") (class "Default")
      (node (ref "R220") (pin "1") (pinfunction "1_1") (pintype "passive"))
      (node (ref "U5") (pin "4") (pinfunction "B2_4") (pintype "passive"))
    )
    (net (code "33") (name "JTAG_TMS_C2M") (class "Default")
      (node (ref "R221") (pin "1") (pinfunction "1_1") (pintype "passive"))
      (node (ref "R224") (pin "2") (pinfunction "2_2") (pintype "passive"))
      (node (ref "U5") (pin "5") (pinfunction "B1_5") (pintype "passive"))
    )
    (net (code "34") (name "MIO36") (class "Default")
      (node (ref "U14") (pin "4") (pinfunction "B2_4") (pintype "passive"))
    )
    (net (code "35") (name "MIO37") (class "Default")
      (node (ref "U14") (pin "5") (pinfunction "B1_5") (pintype "passive"))
    )
    (net (code "36") (name "Net-(J10A-MNT_1)") (class "Default")
      (node (ref "J10") (pin "1") (pinfunction "MNT_1_1") (pintype "passive"))
      (node (ref "J10") (pin "2") (pinfunction "MNT_2_2") (pintype "passive"))
      (node (ref "J10") (pin "3") (pinfunction "MNT_3_3") (pintype "passive"))
      (node (ref "J10") (pin "4") (pinfunction "MNT_4_4") (pintype "passive"))
      (node (ref "R186") (pin "2") (pinfunction "2_2") (pintype "passive"))
    )
    (net (code "37") (name "Net-(J10B-CC1)") (class "Default")
      (node (ref "J10") (pin "A5") (pinfunction "CC1_A5") (pintype "passive"))
      (node (ref "R21") (pin "1") (pinfunction "1_1") (pintype "passive"))
    )
    (net (code "38") (name "Net-(J10C-CC2)") (class "Default")
      (node (ref "J10") (pin "B5") (pinfunction "CC2_B5") (pintype "passive"))
      (node (ref "R26") (pin "1") (pinfunction "1_1") (pintype "passive"))
    )
    (net (code "39") (name "Net-(U10-1B1)") (class "Default")
      (node (ref "R74") (pin "2") (pinfunction "2_2") (pintype "passive"))
      (node (ref "U10") (pin "15") (pinfunction "1B1_15") (pintype "bidirectional"))
    )
    (net (code "40") (name "Net-(U13-EECLK)") (class "Default")
      (node (ref "R80") (pin "1") (pinfunction "1_1") (pintype "passive"))
      (node (ref "U13") (pin "62") (pinfunction "EECLK_62") (pintype "passive"))
      (node (ref "U15") (pin "2") (pinfunction "CLK_2") (pintype "input"))
    )
    (net (code "41") (name "Net-(U13-EECS)") (class "Default")
      (node (ref "R81") (pin "1") (pinfunction "1_1") (pintype "passive"))
      (node (ref "U13") (pin "63") (pinfunction "EECS_63") (pintype "passive"))
      (node (ref "U15") (pin "1") (pinfunction "CS_1") (pintype "input"))
    )
    (net (code "42") (name "Net-(U13-EEDATA)") (class "Default")
      (node (ref "R82") (pin "2") (pinfunction "2_2") (pintype "passive"))
      (node (ref "U13") (pin "61") (pinfunction "EEDATA_61") (pintype "passive"))
      (node (ref "U15") (pin "3") (pinfunction "DI_3") (pintype "input"))
    )
    (net (code "43") (name "Net-(U13-OSCI)") (class "Default")
      (node (ref "C117") (pin "2") (pinfunction "2_2") (pintype "passive"))
      (node (ref "U13") (pin "2") (pinfunction "OSCI_2") (pintype "passive"))
      (node (ref "Y5") (pin "1") (pinfunction "1_Crystal_1") (pintype "passive"))
    )
    (net (code "44") (name "Net-(U13-OSCO)") (class "Default")
      (node (ref "C118") (pin "2") (pinfunction "2_2") (pintype "passive"))
      (node (ref "U13") (pin "3") (pinfunction "OSCO_3") (pintype "passive"))
      (node (ref "Y5") (pin "3") (pinfunction "2_Crystal_3") (pintype "passive"))
    )
    (net (code "45") (name "Net-(U13-REF)") (class "Default")
      (node (ref "R83") (pin "2") (pinfunction "2_2") (pintype "passive"))
      (node (ref "U13") (pin "6") (pinfunction "REF_6") (pintype "passive"))
    )
    (net (code "46") (name "Net-(U13-RESET#)") (class "Default")
      (node (ref "R78") (pin "2") (pinfunction "2_2") (pintype "passive"))
      (node (ref "U13") (pin "14") (pinfunction "RESET#_14") (pintype "passive"))
    )
    (net (code "47") (name "Net-(U15-DO)") (class "Default")
      (node (ref "R79") (pin "1") (pinfunction "1_1") (pintype "passive"))
      (node (ref "R82") (pin "1") (pinfunction "1_1") (pintype "passive"))
      (node (ref "U15") (pin "4") (pinfunction "DO_4") (pintype "output"))
    )
    (net (code "48") (name "P1V8") (class "Default")
      (node (ref "C109") (pin "1") (pinfunction "1_1") (pintype "passive"))
      (node (ref "C92") (pin "1") (pinfunction "1_1") (pintype "passive"))
      (node (ref "C97") (pin "1") (pinfunction "1_1") (pintype "passive"))
      (node (ref "J7") (pin "2") (pinfunction "2_2") (pintype "passive"))
      (node (ref "U10") (pin "12") (pinfunction "2B2_12") (pintype "bidirectional"))
      (node (ref "U10") (pin "13") (pinfunction "2B1_13") (pintype "bidirectional"))
      (node (ref "U10") (pin "2") (pinfunction "VCCB_2") (pintype "power_in"))
      (node (ref "U14") (pin "6") (pinfunction "VCCB_6") (pintype "power_in"))
      (node (ref "U5") (pin "6") (pinfunction "VCCB_6") (pintype "power_in"))
    )
    (net (code "49") (name "P3V3") (class "Default")
      (node (ref "C108") (pin "1") (pinfunction "1_1") (pintype "passive"))
      (node (ref "C111") (pin "1") (pinfunction "1_1") (pintype "passive"))
      (node (ref "C91") (pin "1") (pinfunction "1_1") (pintype "passive"))
      (node (ref "C98") (pin "1") (pinfunction "1_1") (pintype "passive"))
      (node (ref "D4") (pin "2") (pinfunction "K_2") (pintype "passive"))
      (node (ref "D5") (pin "2") (pinfunction "K_2") (pintype "passive"))
      (node (ref "D6") (pin "2") (pinfunction "K_2") (pintype "passive"))
      (node (ref "D7") (pin "2") (pinfunction "K_2") (pintype "passive"))
      (node (ref "U10") (pin "3") (pinfunction "VCCA_3") (pintype "power_in"))
      (node (ref "U14") (pin "7") (pinfunction "VCCA_7") (pintype "power_in"))
      (node (ref "U16") (pin "6") (pinfunction "VCCB_6") (pintype "power_in"))
      (node (ref "U5") (pin "7") (pinfunction "VCCA_7") (pintype "power_in"))
    )
    (net (code "50") (name "PC4_CON_PGND") (class "Default")
      (node (ref "J7") (pin "13") (pinfunction "13_13") (pintype "passive"))
      (node (ref "Q1") (pin "1") (pinfunction "G_1") (pintype "passive"))
      (node (ref "Q2") (pin "3") (pinfunction "D_3") (pintype "passive"))
      (node (ref "R73") (pin "1") (pinfunction "1_1") (pintype "passive"))
    )
    (net (code "51") (name "PS_POR_B") (class "Default")
      (node (ref "U9") (pin "6") (pinfunction "Y1_6") (pintype "open_collector"))
    )
    (net (code "52") (name "PS_SRST_C2M_B") (class "Default")
      (node (ref "J7") (pin "14") (pinfunction "14_14") (pintype "passive"))
      (node (ref "U9") (pin "4") (pinfunction "Y2_4") (pintype "open_collector"))
    )
    (net (code "53") (name "USB_JTAG_DM_N") (class "Default")
      (node (ref "J10") (pin "A7") (pinfunction "Dn1_A7") (pintype "passive"))
      (node (ref "J10") (pin "B7") (pinfunction "Dn2_B7") (pintype "passive"))
      (node (ref "U13") (pin "7") (pinfunction "DM_7") (pintype "passive"))
      (node (ref "U33") (pin "2") (pinfunction "D-_2") (pintype "bidirectional"))
    )
    (net (code "54") (name "USB_JTAG_DM_P") (class "Default")
      (node (ref "J10") (pin "A6") (pinfunction "Dp1_A6") (pintype "passive"))
      (node (ref "J10") (pin "B6") (pinfunction "Dp2_B6") (pintype "passive"))
      (node (ref "U13") (pin "8") (pinfunction "DP_8") (pintype "passive"))
      (node (ref "U33") (pin "1") (pinfunction "D+_1") (pintype "bidirectional"))
    )
    (net (code "55") (name "USB_JTAG_FLTR") (class "Default")
      (node (ref "C105") (pin "1") (pinfunction "1_1") (pintype "passive"))
      (node (ref "C106") (pin "1") (pinfunction "1_1") (pintype "passive"))
      (node (ref "C95") (pin "1") (pinfunction "1_1") (pintype "passive"))
      (node (ref "FB12") (pin "1") (pinfunction "1_1") (pintype "passive"))
      (node (ref "R68") (pin "2") (pinfunction "2_2") (pintype "passive"))
      (node (ref "U7") (pin "5") (pinfunction "EN_5") (pintype "input"))
      (node (ref "U7") (pin "8") (pinfunction "IN_8") (pintype "power_in"))
    )
    (net (code "56") (name "USB_JTAG_GND") (class "Default")
      (node (ref "C107") (pin "2") (pinfunction "2_2") (pintype "passive"))
      (node (ref "FB13") (pin "2") (pinfunction "2_2") (pintype "passive"))
      (node (ref "J10") (pin "A1") (pinfunction "GND_A1") (pintype "power_in"))
      (node (ref "J10") (pin "A12") (pinfunction "GND_A12") (pintype "power_in"))
      (node (ref "J10") (pin "B1") (pinfunction "GND_B1") (pintype "power_in"))
      (node (ref "J10") (pin "B12") (pinfunction "GND_B12") (pintype "power_in"))
      (node (ref "R21") (pin "2") (pinfunction "2_2") (pintype "passive"))
      (node (ref "R26") (pin "2") (pinfunction "2_2") (pintype "passive"))
    )
    (net (code "57") (name "USB_JTAG_VBUS") (class "Default")
      (node (ref "C107") (pin "1") (pinfunction "1_1") (pintype "passive"))
      (node (ref "FB12") (pin "2") (pinfunction "2_2") (pintype "passive"))
      (node (ref "J10") (pin "A4") (pinfunction "VBUS_A4") (pintype "passive"))
      (node (ref "J10") (pin "A9") (pinfunction "VBUS_A9") (pintype "power_in"))
      (node (ref "J10") (pin "B4") (pinfunction "VBUS_B4") (pintype "passive"))
      (node (ref "J10") (pin "B9") (pinfunction "VBUS_B9") (pintype "passive"))
      (node (ref "U33") (pin "6") (pinfunction "VBUS_6") (pintype "passive"))
    )
    (net (code "58") (name "USB_JTAG_VCORE") (class "Default")
      (node (ref "C113") (pin "1") (pinfunction "1_1") (pintype "passive"))
      (node (ref "C114") (pin "1") (pinfunction "1_1") (pintype "passive"))
      (node (ref "C115") (pin "1") (pinfunction "1_1") (pintype "passive"))
      (node (ref "C116") (pin "1") (pinfunction "1_1") (pintype "passive"))
      (node (ref "U13") (pin "12") (pinfunction "VCORE1_12") (pintype "passive"))
      (node (ref "U13") (pin "37") (pinfunction "VOCRE2_37") (pintype "passive"))
      (node (ref "U13") (pin "49") (pinfunction "VREGOUT_49") (pintype "passive"))
      (node (ref "U13") (pin "64") (pinfunction "VCORE3_64") (pintype "passive"))
    )
    (net (code "59") (name "USB_PWRD_VCCIO") (class "Default")
      (node (ref "C103") (pin "1") (pinfunction "1_1") (pintype "passive"))
      (node (ref "C104") (pin "1") (pinfunction "1_1") (pintype "passive"))
      (node (ref "C110") (pin "1") (pinfunction "1_1") (pintype "passive"))
      (node (ref "C112") (pin "1") (pinfunction "1_1") (pintype "passive"))
      (node (ref "C119") (pin "1") (pinfunction "1_1") (pintype "passive"))
      (node (ref "C120") (pin "1") (pinfunction "1_1") (pintype "passive"))
      (node (ref "C121") (pin "1") (pinfunction "1_1") (pintype "passive"))
      (node (ref "C122") (pin "1") (pinfunction "1_1") (pintype "passive"))
      (node (ref "C123") (pin "1") (pinfunction "1_1") (pintype "passive"))
      (node (ref "C93") (pin "2") (pinfunction "2_2") (pintype "passive"))
      (node (ref "C94") (pin "2") (pinfunction "2_2") (pintype "passive"))
      (node (ref "C96") (pin "1") (pinfunction "1_1") (pintype "passive"))
      (node (ref "FB18") (pin "2") (pinfunction "2_2") (pintype "passive"))
      (node (ref "FB19") (pin "2") (pinfunction "2_2") (pintype "passive"))
      (node (ref "R67") (pin "2") (pinfunction "2_2") (pintype "passive"))
      (node (ref "R69") (pin "2") (pinfunction "2_2") (pintype "passive"))
      (node (ref "R71") (pin "2") (pinfunction "2_2") (pintype "passive"))
      (node (ref "R72") (pin "2") (pinfunction "2_2") (pintype "passive"))
      (node (ref "R73") (pin "2") (pinfunction "2_2") (pintype "passive"))
      (node (ref "R76") (pin "2") (pinfunction "2_2") (pintype "passive"))
      (node (ref "R78") (pin "1") (pinfunction "1_1") (pintype "passive"))
      (node (ref "R79") (pin "2") (pinfunction "2_2") (pintype "passive"))
      (node (ref "R80") (pin "2") (pinfunction "2_2") (pintype "passive"))
      (node (ref "R81") (pin "2") (pinfunction "2_2") (pintype "passive"))
      (node (ref "R84") (pin "2") (pinfunction "2_2") (pintype "passive"))
      (node (ref "U10") (pin "4") (pinfunction "1DIR_4") (pintype "input"))
      (node (ref "U11") (pin "1") (pinfunction "DIR2_1") (pintype "input"))
      (node (ref "U11") (pin "10") (pinfunction "DIR1_10") (pintype "input"))
      (node (ref "U11") (pin "6") (pinfunction "VCCB_6") (pintype "power_in"))
      (node (ref "U11") (pin "7") (pinfunction "VCCA_7") (pintype "power_in"))
      (node (ref "U13") (pin "20") (pinfunction "VCCIO1_20") (pintype "passive"))
      (node (ref "U13") (pin "31") (pinfunction "VCCIO2_31") (pintype "passive"))
      (node (ref "U13") (pin "42") (pinfunction "VCCIO3_42") (pintype "passive"))
      (node (ref "U13") (pin "50") (pinfunction "VREGIN_50") (pintype "passive"))
      (node (ref "U13") (pin "56") (pinfunction "VCCIO4_56") (pintype "passive"))
      (node (ref "U14") (pin "10") (pinfunction "DIR1_10") (pintype "input"))
      (node (ref "U15") (pin "8") (pinfunction "VCC_8") (pintype "power_in"))
      (node (ref "U16") (pin "10") (pinfunction "DIR1_10") (pintype "input"))
      (node (ref "U16") (pin "7") (pinfunction "VCCA_7") (pintype "power_in"))
      (node (ref "U5") (pin "10") (pinfunction "DIR1_10") (pintype "input"))
      (node (ref "U7") (pin "1") (pinfunction "OUT_1") (pintype "power_in"))
      (node (ref "U9") (pin "5") (pinfunction "VCC_5") (pintype "power_in"))
    )
    (net (code "60") (name "unconnected-(J7-Pad12)") (class "Default")
      (node (ref "J7") (pin "12") (pinfunction "12_12") (pintype "passive"))
    )
    (net (code "61") (name "unconnected-(U7-NC1-Pad2)") (class "Default")
      (node (ref "U7") (pin "2") (pinfunction "NC1_2") (pintype "passive+no_connect"))
    )
    (net (code "62") (name "unconnected-(U7-NC2-Pad7)") (class "Default")
      (node (ref "U7") (pin "7") (pinfunction "NC2_7") (pintype "passive+no_connect"))
    )
    (net (code "63") (name "unconnected-(U10-2A2-Pad9)") (class "Default")
      (node (ref "U10") (pin "9") (pinfunction "2A2_9") (pintype "bidirectional"))
    )
    (net (code "64") (name "unconnected-(U13-BDBUS2-Pad28)") (class "Default")
      (node (ref "U13") (pin "28") (pinfunction "BDBUS2_28") (pintype "passive+no_connect"))
    )
    (net (code "65") (name "unconnected-(U13-BDBUS3-Pad29)") (class "Default")
      (node (ref "U13") (pin "29") (pinfunction "BDBUS3_29") (pintype "passive+no_connect"))
    )
    (net (code "66") (name "unconnected-(U13-BDBUS4-Pad30)") (class "Default")
      (node (ref "U13") (pin "30") (pinfunction "BDBUS4_30") (pintype "passive+no_connect"))
    )
    (net (code "67") (name "unconnected-(U13-BDBUS5-Pad32)") (class "Default")
      (node (ref "U13") (pin "32") (pinfunction "BDBUS5_32") (pintype "passive+no_connect"))
    )
    (net (code "68") (name "unconnected-(U13-BDBUS6-Pad33)") (class "Default")
      (node (ref "U13") (pin "33") (pinfunction "BDBUS6_33") (pintype "passive+no_connect"))
    )
    (net (code "69") (name "unconnected-(U13-BDBUS7-Pad34)") (class "Default")
      (node (ref "U13") (pin "34") (pinfunction "BDBUS7_34") (pintype "passive+no_connect"))
    )
    (net (code "70") (name "unconnected-(U13-CDBUS2-Pad40)") (class "Default")
      (node (ref "U13") (pin "40") (pinfunction "CDBUS2_40") (pintype "passive+no_connect"))
    )
    (net (code "71") (name "unconnected-(U13-CDBUS3-Pad41)") (class "Default")
      (node (ref "U13") (pin "41") (pinfunction "CDBUS3_41") (pintype "passive+no_connect"))
    )
    (net (code "72") (name "unconnected-(U13-CDBUS4-Pad43)") (class "Default")
      (node (ref "U13") (pin "43") (pinfunction "CDBUS4_43") (pintype "passive+no_connect"))
    )
    (net (code "73") (name "unconnected-(U13-CDBUS5-Pad44)") (class "Default")
      (node (ref "U13") (pin "44") (pinfunction "CDBUS5_44") (pintype "passive+no_connect"))
    )
    (net (code "74") (name "unconnected-(U13-CDBUS6-Pad45)") (class "Default")
      (node (ref "U13") (pin "45") (pinfunction "CDBUS6_45") (pintype "passive+no_connect"))
    )
    (net (code "75") (name "unconnected-(U13-CDBUS7-Pad46)") (class "Default")
      (node (ref "U13") (pin "46") (pinfunction "CDBUS7_46") (pintype "passive+no_connect"))
    )
    (net (code "76") (name "unconnected-(U13-DDBUS0-Pad48)") (class "Default")
      (node (ref "U13") (pin "48") (pinfunction "DDBUS0_48") (pintype "passive+no_connect"))
    )
    (net (code "77") (name "unconnected-(U13-DDBUS2-Pad53)") (class "Default")
      (node (ref "U13") (pin "53") (pinfunction "DDBUS2_53") (pintype "passive+no_connect"))
    )
    (net (code "78") (name "unconnected-(U13-DDBUS3-Pad54)") (class "Default")
      (node (ref "U13") (pin "54") (pinfunction "DDBUS3_54") (pintype "passive+no_connect"))
    )
    (net (code "79") (name "unconnected-(U13-DDBUS4-Pad55)") (class "Default")
      (node (ref "U13") (pin "55") (pinfunction "DDBUS4_55") (pintype "passive+no_connect"))
    )
    (net (code "80") (name "unconnected-(U13-DDBUS5-Pad57)") (class "Default")
      (node (ref "U13") (pin "57") (pinfunction "DDBUS5_57") (pintype "passive+no_connect"))
    )
    (net (code "81") (name "unconnected-(U13-DDBUS6-Pad58)") (class "Default")
      (node (ref "U13") (pin "58") (pinfunction "DDBUS6_58") (pintype "passive+no_connect"))
    )
    (net (code "82") (name "unconnected-(U13-DDBUS7-Pad59)") (class "Default")
      (node (ref "U13") (pin "59") (pinfunction "DDBUS7_59") (pintype "passive+no_connect"))
    )
    (net (code "83") (name "unconnected-(U13-SUSPEND#-Pad36)") (class "Default")
      (node (ref "U13") (pin "36") (pinfunction "SUSPEND#_36") (pintype "passive+no_connect"))
    )
    (net (code "84") (name "unconnected-(U15-NC-Pad7)") (class "Default")
      (node (ref "U15") (pin "7") (pinfunction "NC_7") (pintype "passive+no_connect"))
    )
    (net (code "85") (name "unconnected-(U15-ORG_NC-Pad6)") (class "Default")
      (node (ref "U15") (pin "6") (pinfunction "ORG_NC_6") (pintype "passive+no_connect"))
    )
    (net (code "86") (name "unconnected-(U33-ID-Pad3)") (class "Default")
      (node (ref "U33") (pin "3") (pinfunction "ID_3") (pintype "bidirectional"))
    )
    (net (code "87") (name "unconnected-(U33-NC-Pad5)") (class "Default")
      (node (ref "U33") (pin "5") (pinfunction "NC_5") (pintype "passive"))
    )
  )
)
